# BLETracker_v03.net
KiCad netlist of a schematic drawn in Altium Designer
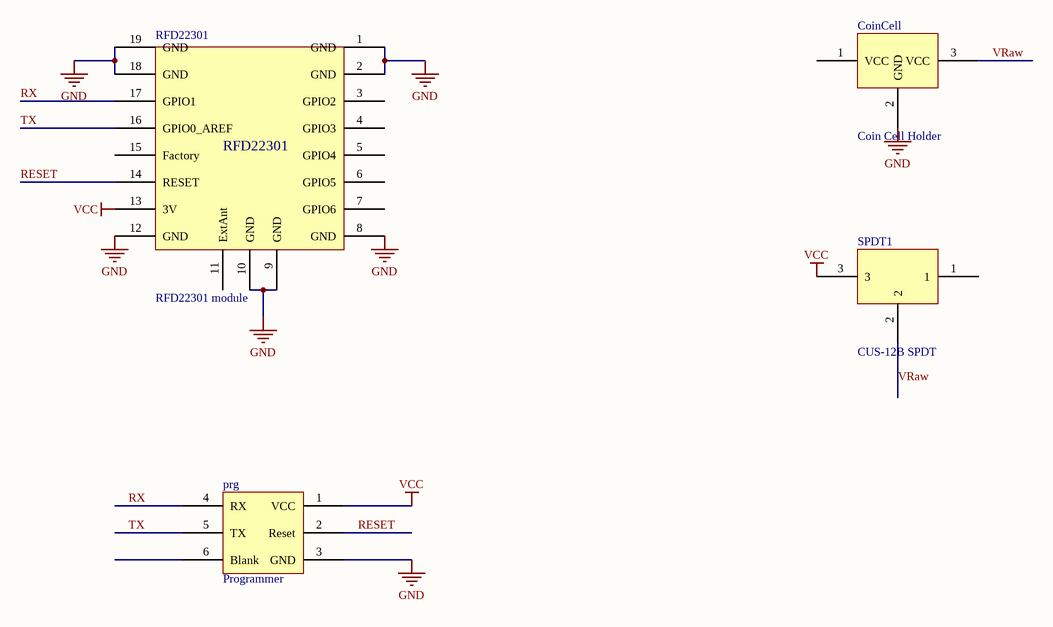
[diagram p0: BLETracker_v03.SchDoc]

(export (version "E")
  (design (tool "Eeschema 10.0.6"))
  (components
    (comp (ref "CoinCell")
      (value "Coin Cell Holder")
      (footprint "CoinCell")
      (libsource (lib "CoinCellHolder") (part "CoinCellHolder"))
    )
    (comp (ref "prg")
      (value "Programmer")
      (footprint "ProgrammingHeader")
      (libsource (lib "ProgrammingHeader") (part "ProgrammingHeader"))
    )
    (comp (ref "RFD22301")
      (value "RFD22301 module")
      (footprint "RFD22301")
      (libsource (lib "RFD22301_Footprint") (part "RFD22301_Footprint"))
    )
    (comp (ref "SPDT1")
      (value "CUS-12B SPDT")
      (footprint "CUS-12B")
      (libsource (lib "CUS-12B_switch") (part "CUS-12B"))
    )
  )
  (nets
    (net (code "1") (name "/RESET") (class "Default")
      (node (ref "RFD22301") (pin "14") (pinfunction "RESET_14") (pintype "passive"))
      (node (ref "prg") (pin "2") (pinfunction "Reset_2") (pintype "passive"))
    )
    (net (code "2") (name "/RX") (class "Default")
      (node (ref "RFD22301") (pin "17") (pinfunction "GPIO1_17") (pintype "passive"))
      (node (ref "prg") (pin "4") (pinfunction "RX_4") (pintype "passive"))
    )
    (net (code "3") (name "/TX") (class "Default")
      (node (ref "RFD22301") (pin "16") (pinfunction "GPIO0_AREF_16") (pintype "passive"))
      (node (ref "prg") (pin "5") (pinfunction "TX_5") (pintype "passive"))
    )
    (net (code "4") (name "/VRaw") (class "Default")
      (node (ref "CoinCell") (pin "3") (pinfunction "VCC_3") (pintype "passive"))
      (node (ref "SPDT1") (pin "2") (pinfunction "2_2") (pintype "passive"))
    )
    (net (code "5") (name "GND") (class "Default")
      (node (ref "CoinCell") (pin "2") (pinfunction "GND_2") (pintype "passive"))
      (node (ref "RFD22301") (pin "1") (pinfunction "GND_1") (pintype "passive"))
      (node (ref "RFD22301") (pin "10") (pinfunction "GND_10") (pintype "passive"))
      (node (ref "RFD22301") (pin "12") (pinfunction "GND_12") (pintype "passive"))
      (node (ref "RFD22301") (pin "18") (pinfunction "GND_18") (pintype "passive"))
      (node (ref "RFD22301") (pin "19") (pinfunction "GND_19") (pintype "passive"))
      (node (ref "RFD22301") (pin "2") (pinfunction "GND_2") (pintype "passive"))
      (node (ref "RFD22301") (pin "8") (pinfunction "GND_8") (pintype "passive"))
      (node (ref "RFD22301") (pin "9") (pinfunction "GND_9") (pintype "passive"))
      (node (ref "prg") (pin "3") (pinfunction "GND_3") (pintype "passive"))
    )
    (net (code "6") (name "VCC") (class "Default")
      (node (ref "RFD22301") (pin "13") (pinfunction "3V_13") (pintype "passive"))
      (node (ref "SPDT1") (pin "3") (pinfunction "3_3") (pintype "passive"))
      (node (ref "prg") (pin "1") (pinfunction "VCC_1") (pintype "passive"))
    )
    (net (code "7") (name "unconnected-(CoinCell-VCC-Pad1)") (class "Default")
      (node (ref "CoinCell") (pin "1") (pinfunction "VCC_1") (pintype "passive"))
    )
    (net (code "8") (name "unconnected-(RFD22301-ExtAnt-Pad11)") (class "Default")
      (node (ref "RFD22301") (pin "11") (pinfunction "ExtAnt_11") (pintype "passive"))
    )
    (net (code "9") (name "unconnected-(RFD22301-Factory-Pad15)") (class "Default")
      (node (ref "RFD22301") (pin "15") (pinfunction "Factory_15") (pintype "passive"))
    )
    (net (code "10") (name "unconnected-(RFD22301-GPIO2-Pad3)") (class "Default")
      (node (ref "RFD22301") (pin "3") (pinfunction "GPIO2_3") (pintype "passive"))
    )
    (net (code "11") (name "unconnected-(RFD22301-GPIO3-Pad4)") (class "Default")
      (node (ref "RFD22301") (pin "4") (pinfunction "GPIO3_4") (pintype "passive"))
    )
    (net (code "12") (name "unconnected-(RFD22301-GPIO4-Pad5)") (class "Default")
      (node (ref "RFD22301") (pin "5") (pinfunction "GPIO4_5") (pintype "passive"))
    )
    (net (code "13") (name "unconnected-(RFD22301-GPIO5-Pad6)") (class "Default")
      (node (ref "RFD22301") (pin "6") (pinfunction "GPIO5_6") (pintype "passive"))
    )
    (net (code "14") (name "unconnected-(RFD22301-GPIO6-Pad7)") (class "Default")
      (node (ref "RFD22301") (pin "7") (pinfunction "GPIO6_7") (pintype "passive"))
    )
    (net (code "15") (name "unconnected-(SPDT1-Pad1)") (class "Default")
      (node (ref "SPDT1") (pin "1") (pinfunction "1_1") (pintype "passive"))
    )
    (net (code "16") (name "unconnected-(prg-Blank-Pad6)") (class "Default")
      (node (ref "prg") (pin "6") (pinfunction "Blank_6") (pintype "passive"))
    )
  )
)
